# agent-mother-sensor.net
KiCad netlist of a schematic drawn in Altium Designer
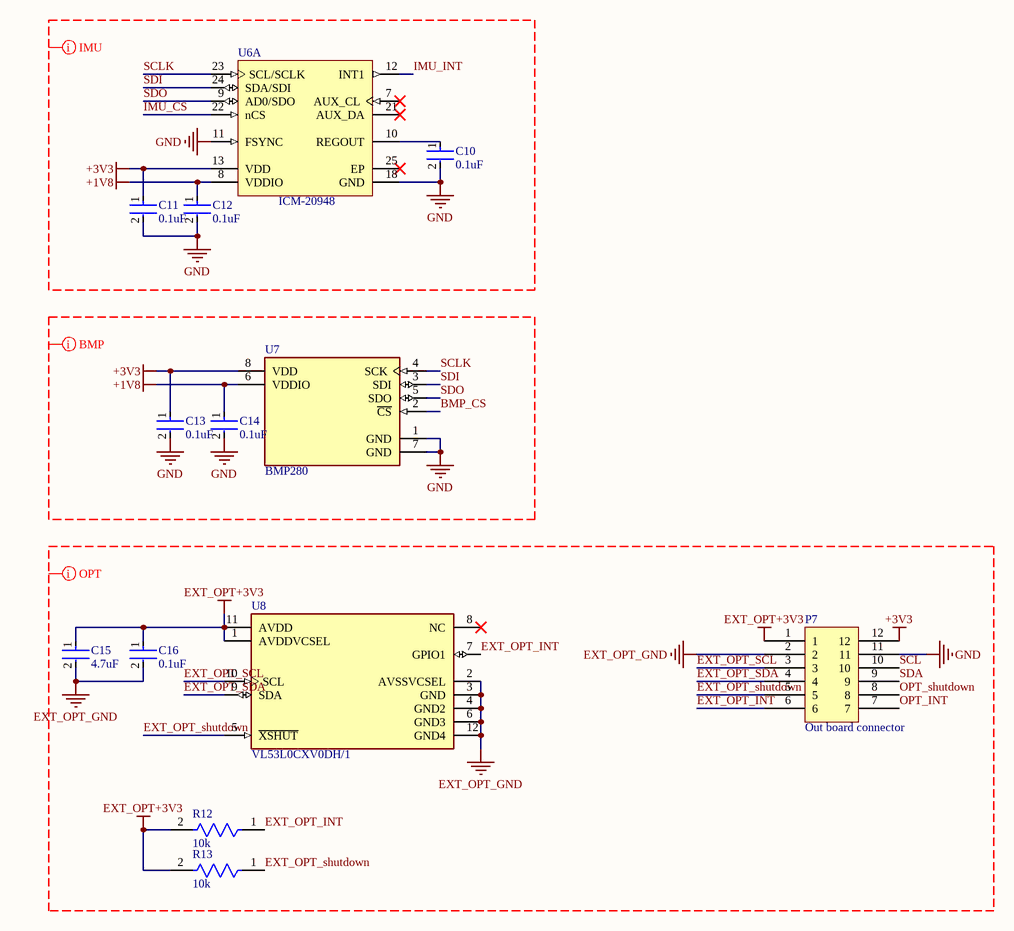
[diagram p0: agent-mother-sensor.SchDoc]

(export (version "E")
  (design (tool "Eeschema 10.0.6"))
  (components
    (comp (ref "C10")
      (value "0.1uF")
      (footprint "FP-C0402-BB-MFG")
      (description "CAP CER 0.1uF 16V X7R 0402")
      (fields
        (field (name "TOLERANCE") "0.1")
        (field (name "OCTOPART") "https://octopart.com/c0402c104k4ractu-kemet-94158")
      )
      (libsource (lib "Altium Content Vault") (part "b4654b650e69147ec39a6b967a45e02"))
    )
    (comp (ref "C11")
      (value "0.1uF")
      (footprint "FP-C0402-BB-MFG")
      (description "CAP CER 0.1uF 16V X7R 0402")
      (fields
        (field (name "TOLERANCE") "0.1")
        (field (name "OCTOPART") "https://octopart.com/c0402c104k4ractu-kemet-94158")
      )
      (libsource (lib "Altium Content Vault") (part "b4654b650e69147ec39a6b967a45e02"))
    )
    (comp (ref "C12")
      (value "0.1uF")
      (footprint "FP-C0402-BB-MFG")
      (description "CAP CER 0.1uF 16V X7R 0402")
      (fields
        (field (name "TOLERANCE") "0.1")
        (field (name "OCTOPART") "https://octopart.com/c0402c104k4ractu-kemet-94158")
      )
      (libsource (lib "Altium Content Vault") (part "b4654b650e69147ec39a6b967a45e02"))
    )
    (comp (ref "C13")
      (value "0.1uF")
      (footprint "FP-C0402-BB-MFG")
      (description "CAP CER 0.1uF 16V X7R 0402")
      (fields
        (field (name "TOLERANCE") "0.1")
        (field (name "OCTOPART") "https://octopart.com/c0402c104k4ractu-kemet-94158")
      )
      (libsource (lib "Altium Content Vault") (part "b4654b650e69147ec39a6b967a45e02"))
    )
    (comp (ref "C14")
      (value "0.1uF")
      (footprint "FP-C0402-BB-MFG")
      (description "CAP CER 0.1uF 16V X7R 0402")
      (fields
        (field (name "TOLERANCE") "0.1")
        (field (name "OCTOPART") "https://octopart.com/c0402c104k4ractu-kemet-94158")
      )
      (libsource (lib "Altium Content Vault") (part "b4654b650e69147ec39a6b967a45e02"))
    )
    (comp (ref "C15")
      (value "4.7uF")
      (footprint "FP-C0402-BB-MFG")
      (description "CAP CER 4.7uF 16V X7R 0402")
      (fields
        (field (name "TOLERANCE") "0.1")
        (field (name "OCTOPART") "https://octopart.com/c0402c104k4ractu-kemet-94158")
      )
      (libsource (lib "Altium Content Vault") (part "b4654b650e69147ec39a6b967a45e02"))
    )
    (comp (ref "C16")
      (value "0.1uF")
      (footprint "FP-C0402-BB-MFG")
      (description "CAP CER 0.1uF 16V X7R 0402")
      (fields
        (field (name "TOLERANCE") "0.1")
        (field (name "OCTOPART") "https://octopart.com/c0402c104k4ractu-kemet-94158")
      )
      (libsource (lib "Altium Content Vault") (part "b4654b650e69147ec39a6b967a45e02"))
    )
    (comp (ref "P7")
      (value "Out board connector")
      (footprint "Edge Connector")
      (description "6 pins pcb connector")
      (libsource (lib "TVMD") (part "Out board connector"))
    )
    (comp (ref "R12")
      (value "10k")
      (footprint "FP-CRCW0402-e3-IPC_A")
      (description "RES Thick Film, 10kΩ, 0.063W, 0402")
      (fields (field (name "TOLERANCE") "5%"))
      (libsource (lib "Altium Content Vault") (part "1029c3af85768c4190bb7ad29bc67b5"))
    )
    (comp (ref "R13")
      (value "10k")
      (footprint "FP-CRCW0402-e3-IPC_A")
      (description "RES Thick Film, 10kΩ, 0.063W, 0402")
      (fields (field (name "TOLERANCE") "5%"))
      (libsource (lib "Altium Content Vault") (part "1029c3af85768c4190bb7ad29bc67b5"))
    )
    (comp (ref "U6")
      (value "ICM-20948")
      (footprint "TDK-QFN-24_L")
      (fields (field (name "MANUFACTURER") "TDK"))
      (libsource (lib "Altium Content Vault") (part "TDK-ICM-20948-QFN-24"))
    )
    (comp (ref "U7")
      (value "BMP280")
      (footprint "FP-BMP280-MFG")
      (description "SENSOR PRESSURE ABS")
      (libsource (lib "Altium Content Vault") (part "69b1aacbb03d82763a43fac02afba64"))
    )
    (comp (ref "U8")
      (value "VL53L0CXV0DH/1")
      (footprint "FP-LGA-12-MFG")
      (description "SENSOR OPTICAL 200CM I2C")
      (fields
        (field (name "OCTOPART") "https://octopart.com/vl53l0cxv0dh%2F1-stmicroelectronics-71168165")
        (field (name "MANUFACTURER") "STMicroelectronics")
      )
      (libsource (lib "Altium Content Vault") (part "be96beb80d1391f21c16cbc96e60673"))
    )
  )
  (nets
    (net (code "1") (name "+1V8") (class "Default")
      (node (ref "C12") (pin "1") (pinfunction "1_1") (pintype "passive"))
      (node (ref "C14") (pin "1") (pinfunction "1_1") (pintype "passive"))
      (node (ref "U6") (pin "8") (pinfunction "VDDIO_8") (pintype "power_in"))
      (node (ref "U7") (pin "6") (pinfunction "VDDIO_6") (pintype "power_in"))
    )
    (net (code "2") (name "+3V3") (class "Default")
      (node (ref "C11") (pin "1") (pinfunction "1_1") (pintype "passive"))
      (node (ref "C13") (pin "1") (pinfunction "1_1") (pintype "passive"))
      (node (ref "P7") (pin "12") (pinfunction "12_12") (pintype "passive"))
      (node (ref "U6") (pin "13") (pinfunction "VDD_13") (pintype "power_in"))
      (node (ref "U7") (pin "8") (pinfunction "VDD_8") (pintype "power_in"))
    )
    (net (code "3") (name "/BMP_CS") (class "Default")
      (node (ref "U7") (pin "2") (pinfunction "~{CS}_2") (pintype "input"))
    )
    (net (code "4") (name "/EXT_OPT_INT") (class "Default")
      (node (ref "P7") (pin "6") (pinfunction "6_6") (pintype "passive"))
      (node (ref "R12") (pin "1") (pinfunction "1_1") (pintype "passive"))
      (node (ref "U8") (pin "7") (pinfunction "GPIO1_7") (pintype "bidirectional"))
    )
    (net (code "5") (name "/EXT_OPT_SCL") (class "Default")
      (node (ref "P7") (pin "3") (pinfunction "3_3") (pintype "passive"))
      (node (ref "U8") (pin "10") (pinfunction "SCL_10") (pintype "input"))
    )
    (net (code "6") (name "/EXT_OPT_SDA") (class "Default")
      (node (ref "P7") (pin "4") (pinfunction "4_4") (pintype "passive"))
      (node (ref "U8") (pin "9") (pinfunction "SDA_9") (pintype "bidirectional"))
    )
    (net (code "7") (name "/EXT_OPT_shutdown") (class "Default")
      (node (ref "P7") (pin "5") (pinfunction "5_5") (pintype "passive"))
      (node (ref "R13") (pin "1") (pinfunction "1_1") (pintype "passive"))
      (node (ref "U8") (pin "5") (pinfunction "~{XSHUT}_5") (pintype "input"))
    )
    (net (code "8") (name "/IMU_CS") (class "Default")
      (node (ref "U6") (pin "22") (pinfunction "nCS_22") (pintype "input"))
    )
    (net (code "9") (name "/IMU_INT") (class "Default")
      (node (ref "U6") (pin "12") (pinfunction "INT1_12") (pintype "output"))
    )
    (net (code "10") (name "/OPT_INT") (class "Default")
      (node (ref "P7") (pin "7") (pinfunction "7_7") (pintype "passive"))
    )
    (net (code "11") (name "/OPT_shutdown") (class "Default")
      (node (ref "P7") (pin "8") (pinfunction "8_8") (pintype "passive"))
    )
    (net (code "12") (name "/SCL") (class "Default")
      (node (ref "P7") (pin "10") (pinfunction "10_10") (pintype "passive"))
    )
    (net (code "13") (name "/SCLK") (class "Default")
      (node (ref "U6") (pin "23") (pinfunction "SCL/SCLK_23") (pintype "input"))
      (node (ref "U7") (pin "4") (pinfunction "SCK_4") (pintype "input"))
    )
    (net (code "14") (name "/SDA") (class "Default")
      (node (ref "P7") (pin "9") (pinfunction "9_9") (pintype "passive"))
    )
    (net (code "15") (name "/SDI") (class "Default")
      (node (ref "U6") (pin "24") (pinfunction "SDA/SDI_24") (pintype "bidirectional"))
      (node (ref "U7") (pin "3") (pinfunction "SDI_3") (pintype "bidirectional"))
    )
    (net (code "16") (name "/SDO") (class "Default")
      (node (ref "U6") (pin "9") (pinfunction "AD0/SDO_9") (pintype "bidirectional"))
      (node (ref "U7") (pin "5") (pinfunction "SDO_5") (pintype "bidirectional"))
    )
    (net (code "17") (name "EXT_OPT+3V3") (class "Default")
      (node (ref "C15") (pin "1") (pinfunction "1_1") (pintype "passive"))
      (node (ref "C16") (pin "1") (pinfunction "1_1") (pintype "passive"))
      (node (ref "P7") (pin "1") (pinfunction "1_1") (pintype "passive"))
      (node (ref "R12") (pin "2") (pinfunction "2_2") (pintype "passive"))
      (node (ref "R13") (pin "2") (pinfunction "2_2") (pintype "passive"))
      (node (ref "U8") (pin "1") (pinfunction "AVDDVCSEL_1") (pintype "power_in"))
      (node (ref "U8") (pin "11") (pinfunction "AVDD_11") (pintype "power_in"))
    )
    (net (code "18") (name "EXT_OPT_GND") (class "Default")
      (node (ref "C15") (pin "2") (pinfunction "2_2") (pintype "passive"))
      (node (ref "C16") (pin "2") (pinfunction "2_2") (pintype "passive"))
      (node (ref "P7") (pin "2") (pinfunction "2_2") (pintype "passive"))
      (node (ref "U8") (pin "12") (pinfunction "GND4_12") (pintype "power_in"))
      (node (ref "U8") (pin "2") (pinfunction "AVSSVCSEL_2") (pintype "power_in"))
      (node (ref "U8") (pin "3") (pinfunction "GND_3") (pintype "power_in"))
      (node (ref "U8") (pin "4") (pinfunction "GND2_4") (pintype "power_in"))
      (node (ref "U8") (pin "6") (pinfunction "GND3_6") (pintype "power_in"))
    )
    (net (code "19") (name "GND") (class "Default")
      (node (ref "C10") (pin "2") (pinfunction "2_2") (pintype "passive"))
      (node (ref "C11") (pin "2") (pinfunction "2_2") (pintype "passive"))
      (node (ref "C12") (pin "2") (pinfunction "2_2") (pintype "passive"))
      (node (ref "C13") (pin "2") (pinfunction "2_2") (pintype "passive"))
      (node (ref "C14") (pin "2") (pinfunction "2_2") (pintype "passive"))
      (node (ref "P7") (pin "11") (pinfunction "11_11") (pintype "passive"))
      (node (ref "U6") (pin "11") (pinfunction "FSYNC_11") (pintype "input"))
      (node (ref "U6") (pin "18") (pinfunction "GND_18") (pintype "power_in"))
      (node (ref "U7") (pin "1") (pinfunction "GND_1") (pintype "power_in"))
      (node (ref "U7") (pin "7") (pinfunction "GND_7") (pintype "power_in"))
    )
    (net (code "20") (name "Net-(U6A-REGOUT)") (class "Default")
      (node (ref "C10") (pin "1") (pinfunction "1_1") (pintype "passive"))
      (node (ref "U6") (pin "10") (pinfunction "REGOUT_10") (pintype "passive"))
    )
    (net (code "21") (name "unconnected-(U6A-AUX_CL-Pad7)") (class "Default")
      (node (ref "U6") (pin "7") (pinfunction "AUX_CL_7") (pintype "input+no_connect"))
    )
    (net (code "22") (name "unconnected-(U6A-AUX_DA-Pad21)") (class "Default")
      (node (ref "U6") (pin "21") (pinfunction "AUX_DA_21") (pintype "passive+no_connect"))
    )
    (net (code "23") (name "unconnected-(U6A-EP-Pad25)") (class "Default")
      (node (ref "U6") (pin "25") (pinfunction "EP_25") (pintype "passive+no_connect"))
    )
    (net (code "24") (name "unconnected-(U8-NC-Pad8)") (class "Default")
      (node (ref "U8") (pin "8") (pinfunction "NC_8") (pintype "passive+no_connect"))
    )
  )
)
